# 31-FT4232_UART_TO_USB_BRIDG.net
KiCad netlist of a schematic drawn in Altium Designer
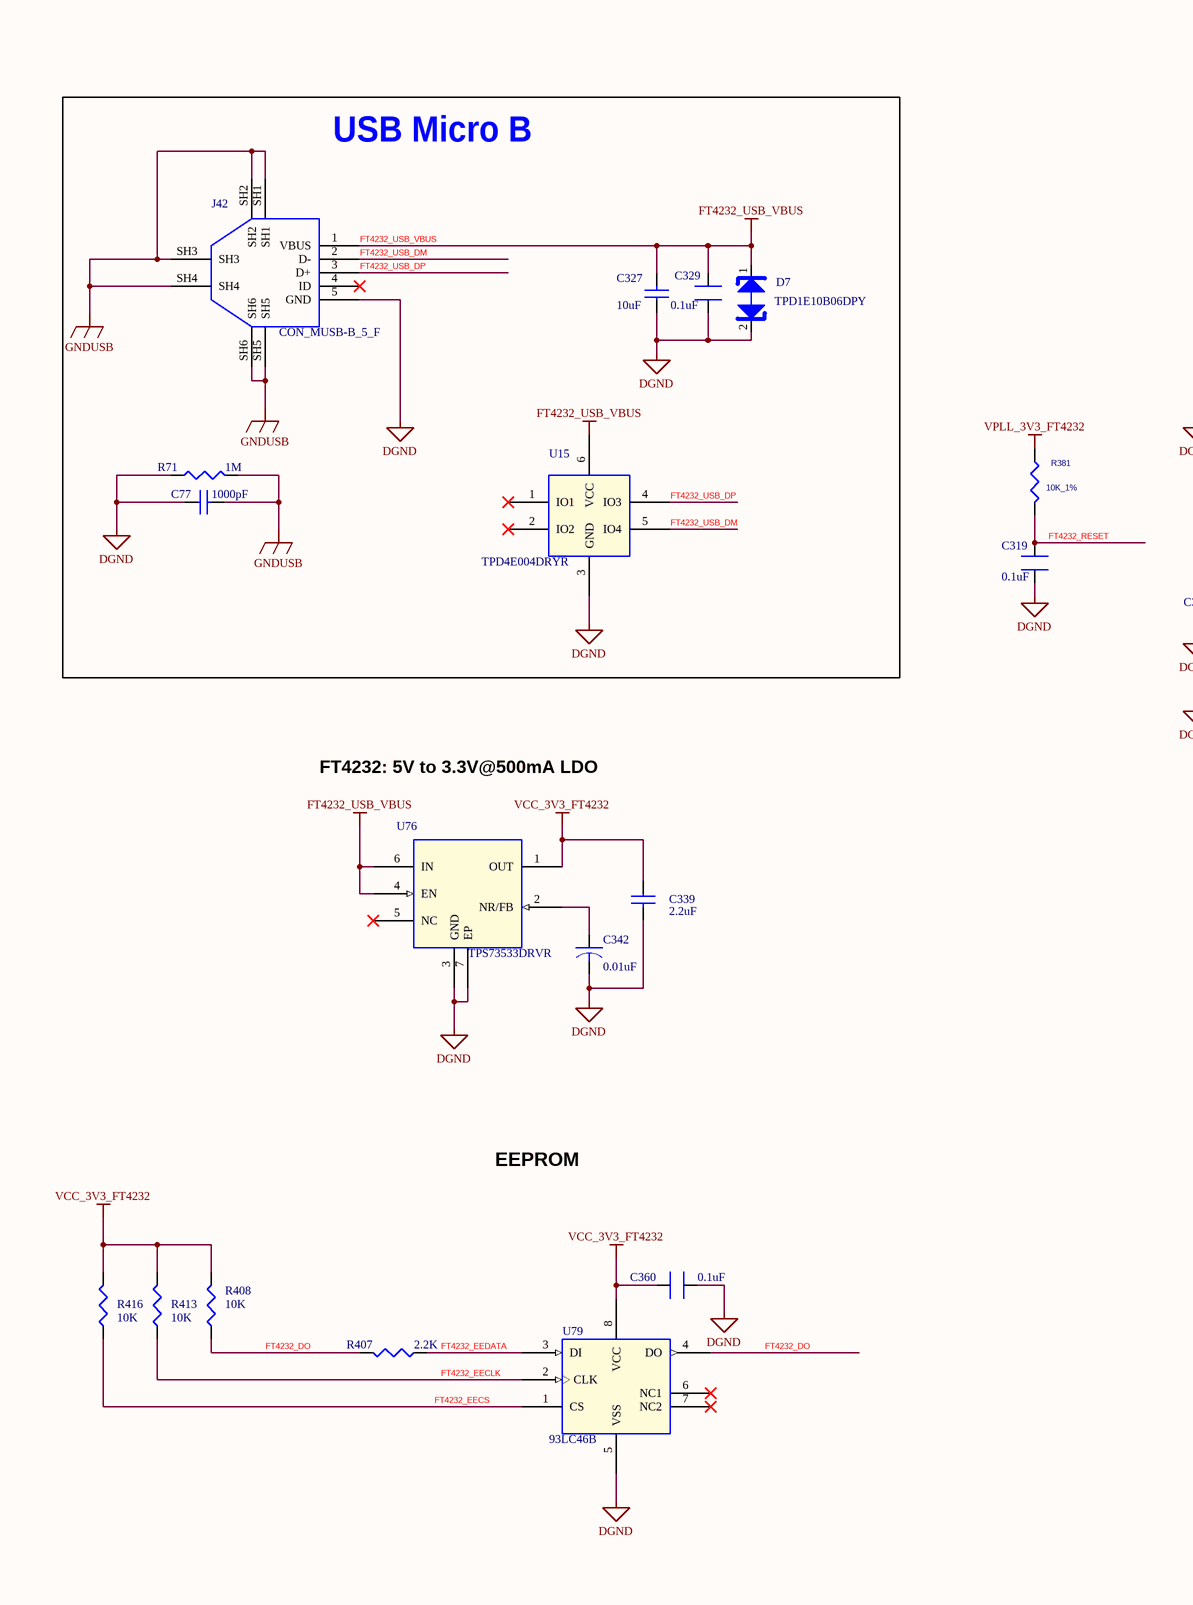
[diagram p0: 31-FT4232 UART TO USB BRIDG.SchDoc, left]
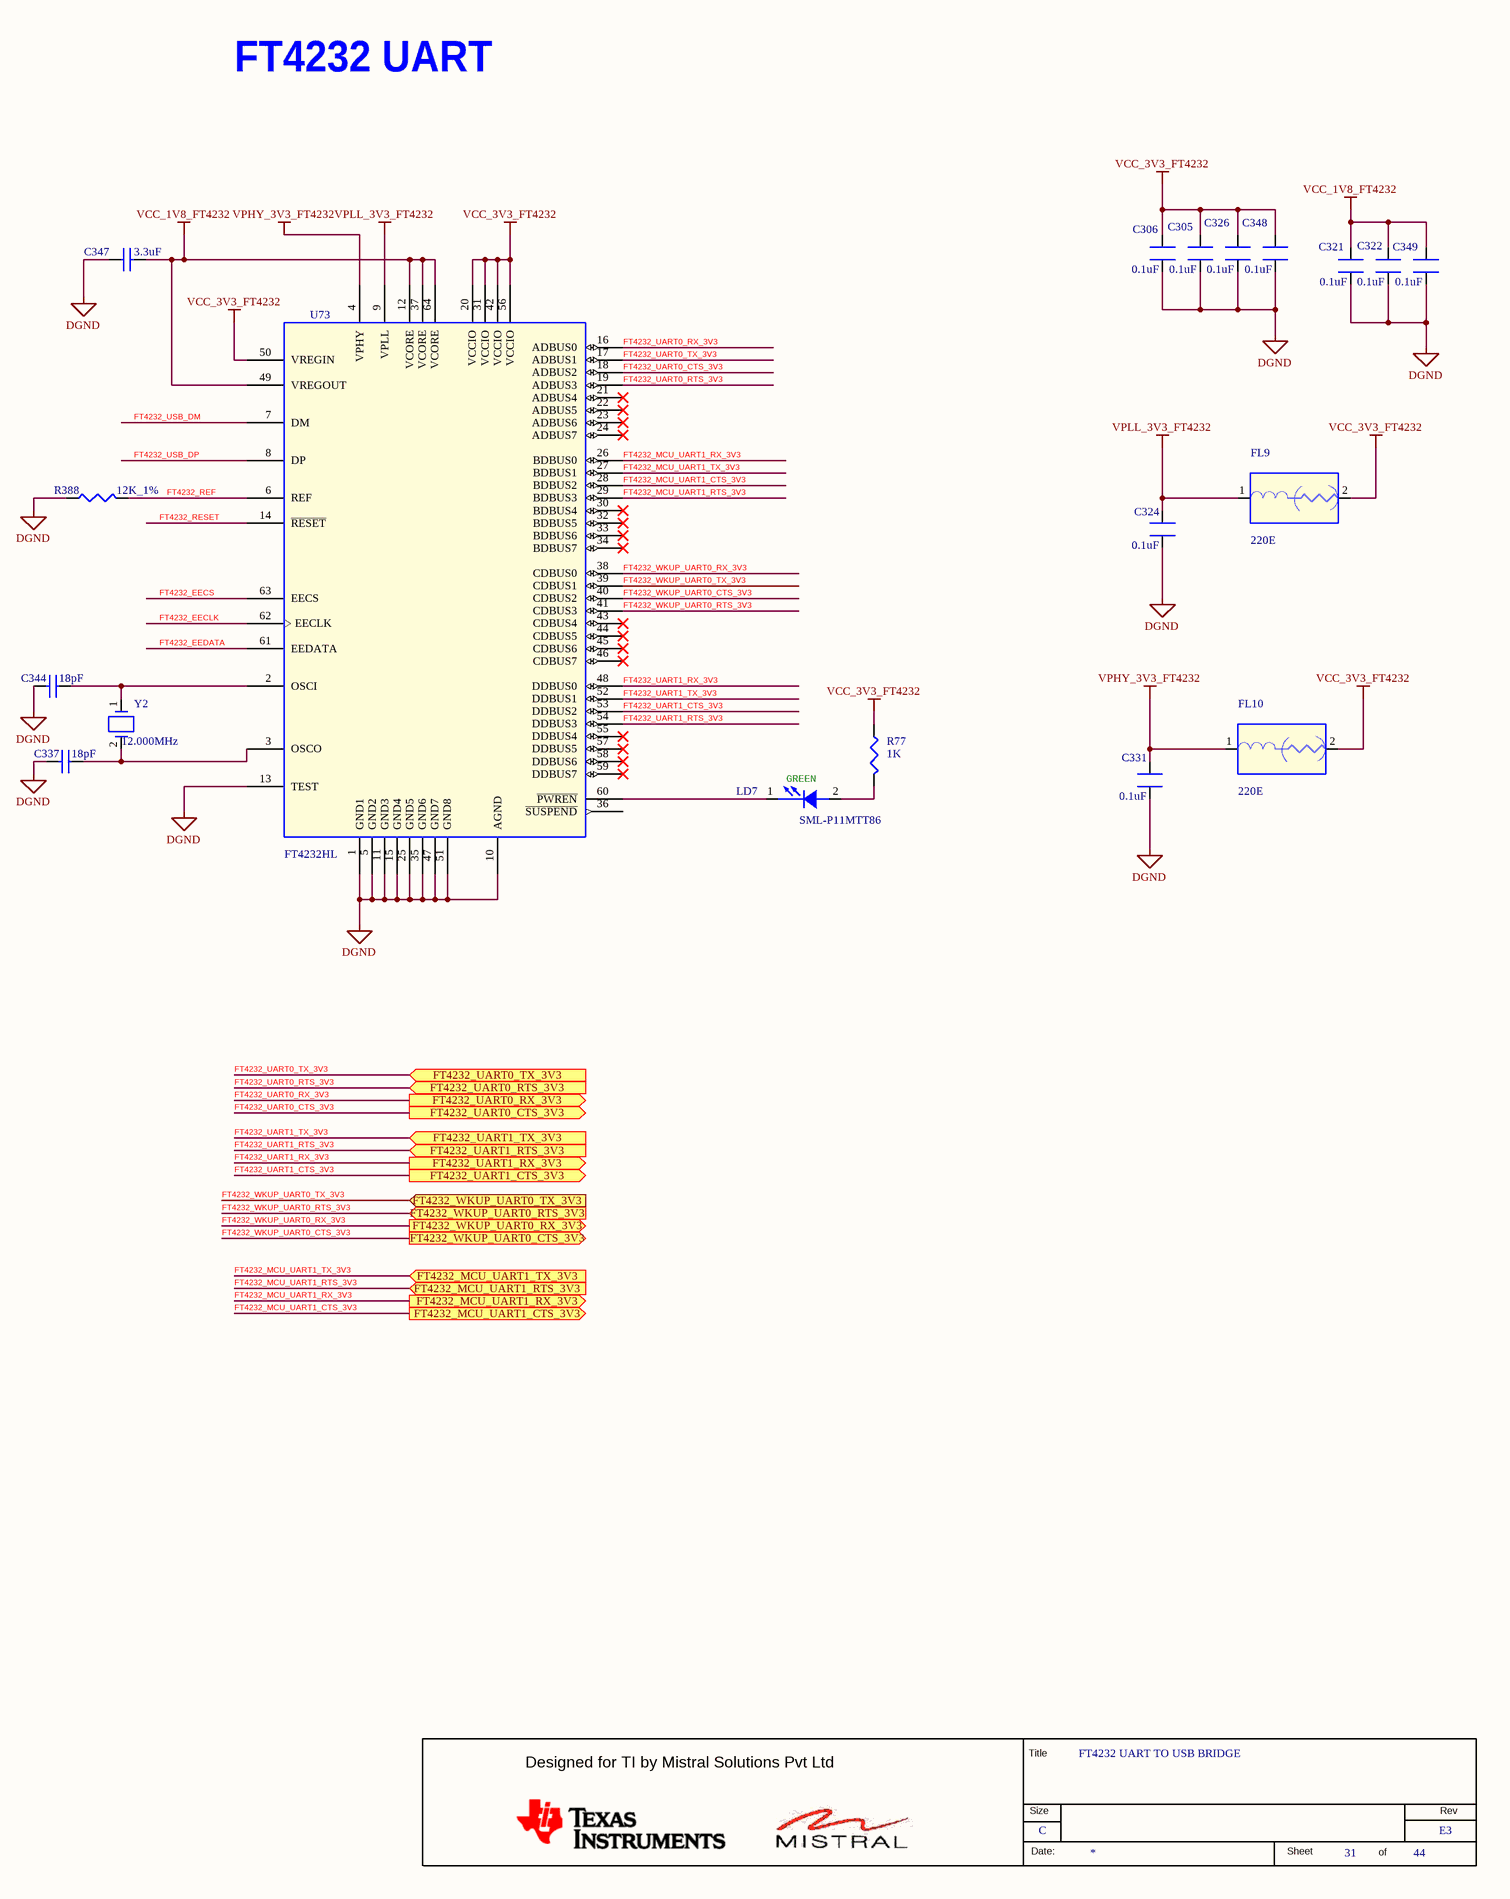
[diagram p1: 31-FT4232 UART TO USB BRIDG.SchDoc, right]

(export (version "E")
  (design (tool "Eeschema 10.0.6"))
  (components
    (comp (ref "C77")
      (value "1000pF")
      (footprint "CAP1206")
      (description "CAP CERAMIC 1000pF 2KV 10% X7R 1206")
      (fields (field (name "DISTRIBUTOR_PART_NUMBER") "478-2956-1-ND") (field (name "VOLTAGE") "2KV"))
      (libsource (lib "*") (part "CAP_Dup5"))
    )
    (comp (ref "C305")
      (value "0.1uF")
      (footprint "TMDX654GPEVM_BRD:CAP0201_0-5")
      (description "CAP CERAMIC 0.1uF 16V 10% X5R 0201")
      (fields
        (field (name "MISTRAL PART NO") "120009030072-R")
        (field (name "MFR_PART_NUMBER") "GRM033R61C104KE84J")
      )
      (libsource (lib "*") (part "CAP_Dup3"))
    )
    (comp (ref "C306")
      (value "0.1uF")
      (footprint "TMDX654GPEVM_BRD:CAP0201_0-5")
      (description "CAP CERAMIC 0.1uF 16V 10% X5R 0201")
      (fields (field (name "DISTRIBUTOR_PART_NUMBER") "490-16742-1-ND") (field (name "VOLTAGE") "16V"))
      (libsource (lib "*") (part "CAP_Dup3"))
    )
    (comp (ref "C319")
      (value "0.1uF")
      (footprint "TMDX654GPEVM_BRD:CAP0201_0-5")
      (description "CAP CERAMIC 0.1uF 16V 10% X5R 0201")
      (fields (field (name "DISTRIBUTOR_PART_NUMBER") "490-16742-1-ND") (field (name "VOLTAGE") "16V"))
      (libsource (lib "*") (part "CAP_Dup3"))
    )
    (comp (ref "C321")
      (value "0.1uF")
      (footprint "TMDX654GPEVM_BRD:CAP0201_0-5")
      (description "CAP CERAMIC 0.1uF 16V 10% X5R 0201")
      (fields
        (field (name "MISTRAL PART NO") "120009030072-R")
        (field (name "MFR_PART_NUMBER") "GRM033R61C104KE84J")
      )
      (libsource (lib "*") (part "CAP_Dup3"))
    )
    (comp (ref "C322")
      (value "0.1uF")
      (footprint "TMDX654GPEVM_BRD:CAP0201_0-5")
      (description "CAP CERAMIC 0.1uF 16V 10% X5R 0201")
      (fields (field (name "DISTRIBUTOR_PART_NUMBER") "490-16742-1-ND") (field (name "VOLTAGE") "16V"))
      (libsource (lib "*") (part "CAP_Dup3"))
    )
    (comp (ref "C324")
      (value "0.1uF")
      (footprint "TMDX654GPEVM_BRD:CAP0201_0-5")
      (description "CAP CERAMIC 0.1uF 16V 10% X5R 0201")
      (fields
        (field (name "MISTRAL PART NO") "120009030072-R")
        (field (name "MFR_PART_NUMBER") "GRM033R61C104KE84J")
      )
      (libsource (lib "*") (part "CAP_Dup3"))
    )
    (comp (ref "C326")
      (value "0.1uF")
      (footprint "TMDX654GPEVM_BRD:CAP0201_0-5")
      (description "CAP CERAMIC 0.1uF 16V 10% X5R 0201")
      (fields
        (field (name "MISTRAL PART NO") "120009030072-R")
        (field (name "MFR_PART_NUMBER") "GRM033R61C104KE84J")
      )
      (libsource (lib "*") (part "CAP_Dup3"))
    )
    (comp (ref "C327")
      (value "10uF")
      (footprint "CAP0603_1")
      (description "CAP CERAMIC 10uF 10V 10% X5R 0603")
      (fields (field (name "DISTRIBUTOR_PART_NUMBER") "478-10766-1-ND") (field (name "VOLTAGE") "10V"))
      (libsource (lib "*") (part "CAP_Dup5"))
    )
    (comp (ref "C329")
      (value "0.1uF")
      (footprint "TMDX654GPEVM_BRD:CAP0201_0-5")
      (description "CAP CERAMIC 0.1uF 16V 10% X5R 0201")
      (fields
        (field (name "MISTRAL PART NO") "120009030072-R")
        (field (name "MFR_PART_NUMBER") "GRM033R61C104KE84J")
      )
      (libsource (lib "*") (part "CAP_Dup3"))
    )
    (comp (ref "C331")
      (value "0.1uF")
      (footprint "TMDX654GPEVM_BRD:CAP0201_0-5")
      (description "CAP CERAMIC 0.1uF 16V 10% X5R 0201")
      (fields (field (name "DISTRIBUTOR_PART_NUMBER") "490-16742-1-ND") (field (name "VOLTAGE") "16V"))
      (libsource (lib "*") (part "CAP_Dup3"))
    )
    (comp (ref "C337")
      (value "18pF")
      (footprint "CAP0402_0-75")
      (description "CAP CERAMIC 18pF 50V 5% C0G(NP0) 0402")
      (fields (field (name "DISTRIBUTOR_PART_NUMBER") "490-5858-1-ND") (field (name "VOLTAGE") "50V"))
      (libsource (lib "*") (part "CAP_Dup5"))
    )
    (comp (ref "C339")
      (value "2.2uF")
      (footprint "CAP0402_0-75")
      (description "CAP CERAMIC 2.2uF 10V 20% X5R 0402")
      (fields (field (name "DISTRIBUTOR_PART_NUMBER") "490-12254-1-ND") (field (name "VOLTAGE") "10V"))
      (libsource (lib "*") (part "CAP_Dup5"))
    )
    (comp (ref "C342")
      (value "0.01uF")
      (footprint "CAP0201_0-5")
      (description "CAP CERAMIC 0.01uF 25V 10% X5R 0201")
      (fields (field (name "DISTRIBUTOR_PART_NUMBER") "GRM033R61E103KA12J-ND") (field (name "VOLTAGE") "25V"))
      (libsource (lib "*") (part "CAP"))
    )
    (comp (ref "C344")
      (value "18pF")
      (footprint "CAP0402_0-75")
      (description "CAP CERAMIC 18pF 50V 5% C0G(NP0) 0402")
      (fields
        (field (name "MISTRAL PART NO") "120014050002-R")
        (field (name "MFR_PART_NUMBER") "GRM1555C1H180JA01D")
      )
      (libsource (lib "*") (part "CAP_Dup5"))
    )
    (comp (ref "C347")
      (value "3.3uF")
      (footprint "CAP0402")
      (description "CAP CERAMIC 3.3uF 6.3V 20% X5R 0402")
      (fields (field (name "DISTRIBUTOR_PART_NUMBER") "445-7394-1-ND") (field (name "VOLTAGE") "6.3V"))
      (libsource (lib "*") (part "CAP_Dup5"))
    )
    (comp (ref "C348")
      (value "0.1uF")
      (footprint "TMDX654GPEVM_BRD:CAP0201_0-5")
      (description "CAP CERAMIC 0.1uF 16V 10% X5R 0201")
      (fields (field (name "DISTRIBUTOR_PART_NUMBER") "490-16742-1-ND") (field (name "VOLTAGE") "16V"))
      (libsource (lib "*") (part "CAP_Dup3"))
    )
    (comp (ref "C349")
      (value "0.1uF")
      (footprint "TMDX654GPEVM_BRD:CAP0201_0-5")
      (description "CAP CERAMIC 0.1uF 16V 10% X5R 0201")
      (fields (field (name "DISTRIBUTOR_PART_NUMBER") "490-16742-1-ND") (field (name "VOLTAGE") "16V"))
      (libsource (lib "*") (part "CAP_Dup3"))
    )
    (comp (ref "C360")
      (value "0.1uF")
      (footprint "TMDX654GPEVM_BRD:CAP0201_0-5")
      (description "CAP CERAMIC 0.1uF 16V 10% X5R 0201")
      (fields (field (name "DISTRIBUTOR_PART_NUMBER") "490-16742-1-ND") (field (name "VOLTAGE") "16V"))
      (libsource (lib "*") (part "CAP_Dup3"))
    )
    (comp (ref "D7")
      (value "TPD1E10B06DPY")
      (footprint "DIO_DFN0402")
      (description "DIODE 1CH ESD PROTECTION SMD(0402)")
      (fields (field (name "DISTRIBUTOR_PART_NUMBER") "296-30406-1-ND") (field (name "VOLTAGE") "NA"))
      (libsource (lib "*") (part "DIODE_PESD"))
    )
    (comp (ref "FL9")
      (value "220E")
      (footprint "EMIFIL_BLM15A_0402")
      (description "FERRITE CHIP 220E 0.3A 0402")
      (fields (field (name "DISTRIBUTOR_PART_NUMBER") "490-5197-1-ND") (field (name "VOLTAGE") "NA"))
      (libsource (lib "*") (part "EMIFILTER_IND"))
    )
    (comp (ref "FL10")
      (value "220E")
      (footprint "EMIFIL_BLM15A_0402")
      (description "FERRITE CHIP 220E 0.3A 0402")
      (fields
        (field (name "MISTRAL PART NO") "130013100020-R")
        (field (name "MFR_PART_NUMBER") "BLM15GG221SN1D")
      )
      (libsource (lib "*") (part "EMIFILTER_IND"))
    )
    (comp (ref "J42")
      (value "CON_MUSB-B_5_F")
      (footprint "CON_MUSBB5_1051640001_S_R_S_2-5")
      (description "CON MICRO USB-B TYPE 5POS FEMALE RT SMD")
      (fields (field (name "DISTRIBUTOR_PART_NUMBER") "WM11263CT-ND") (field (name "VOLTAGE") "NA"))
      (libsource (lib "*") (part "CON_MUSB-B_5_1051640001"))
    )
    (comp (ref "LD7")
      (value "SML-P11MTT86")
      (footprint "LED_0402_0-3")
      (description "DIODE LED GREEN 0402")
      (fields (field (name "VOLTAGE") "NA") (field (name "MISTRAL PART NO") "130010060029-R"))
      (libsource (lib "*") (part "DIODE_LED"))
    )
    (comp (ref "R71")
      (value "1M")
      (footprint "RES0603_0-75")
      (description "RES 1M 1/10W 5% 0603")
      (fields
        (field (name "MISTRAL PART NO") "110009030413-R")
        (field (name "MFR_PART_NUMBER") "ERJ-3GEYJ105V")
      )
      (libsource (lib "*") (part "RESISTOR_Dup5"))
    )
    (comp (ref "R77")
      (value "1K")
      (footprint "RES0201")
      (description "RES 1K 1/20W 5% 0201")
      (fields
        (field (name "MISTRAL PART NO") "110015080014-R")
        (field (name "MFR_PART_NUMBER") "CRCW02011K00FKED")
      )
      (libsource (lib "*") (part "RESISTOR_Dup5"))
    )
    (comp (ref "R381")
      (value "10K_1%")
      (footprint "RES0402_0-5")
      (description "RES 10K 1/16W 1% 0402")
      (fields (field (name "VOLTAGE") "NA") (field (name "MISTRAL PART NO") "110009030220-P"))
      (libsource (lib "*") (part "RESISTOR_Dup2"))
    )
    (comp (ref "R388")
      (value "12K_1%")
      (footprint "RES0402")
      (description "RES 12K 1/16W 1% 0402")
      (fields (field (name "DISTRIBUTOR_PART_NUMBER") "P12.0KLCT-ND") (field (name "VOLTAGE") "NA"))
      (libsource (lib "*") (part "RESISTOR_Dup5"))
    )
    (comp (ref "R407")
      (value "2.2K")
      (footprint "RES0402_0-5")
      (description "RES 2.2K 1/16W 5% 0402")
      (fields (field (name "DISTRIBUTOR_PART_NUMBER") "311-2.2KJRCT-ND") (field (name "VOLTAGE") "NA"))
      (libsource (lib "*") (part "RESISTOR_Dup5"))
    )
    (comp (ref "R408")
      (value "10K")
      (footprint "RES0402_0-5")
      (description "RES 10K 1/16W 5% 0402")
      (fields
        (field (name "MISTRAL PART NO") "110009030208-R")
        (field (name "MFR_PART_NUMBER") "RC0402JR-0710KL")
      )
      (libsource (lib "*") (part "RESISTOR_Dup5"))
    )
    (comp (ref "R413")
      (value "10K")
      (footprint "RES0402_0-5")
      (description "RES 10K 1/16W 5% 0402")
      (fields
        (field (name "MISTRAL PART NO") "110009030208-R")
        (field (name "MFR_PART_NUMBER") "RC0402JR-0710KL")
      )
      (libsource (lib "*") (part "RESISTOR_Dup5"))
    )
    (comp (ref "R416")
      (value "10K")
      (footprint "RES0402_0-5")
      (description "RES 10K 1/16W 5% 0402")
      (fields (field (name "DISTRIBUTOR_PART_NUMBER") "311-10KJRCT-ND") (field (name "VOLTAGE") "NA"))
      (libsource (lib "*") (part "RESISTOR_Dup5"))
    )
    (comp (ref "U15")
      (value "TPD4E004DRYR")
      (footprint "SON6_19-68_60X45")
      (description "IC 4CH ESD-PROT ARRAY SON6")
      (fields
        (field (name "DISTRIBUTOR_PART_NUMBER") "296-23618-1-ND")
        (field (name "MISTRAL PART NO") "141010020012-P")
      )
      (libsource (lib "*") (part "TPD4E004_SON6"))
    )
    (comp (ref "U73")
      (value "FT4232HL")
      (footprint "TMDX654GPEVM_BRD:LQFP64_19-68_390X390_1-6")
      (description "IC HIGH SPEED QUAD USB UART LQFP64")
      (fields
        (field (name "MISTRAL PART NO") "141013080006-R")
        (field (name "MFR_PART_NUMBER") "FT4232HL-REEL")
      )
      (libsource (lib "*") (part "FT4232H _LQFP64"))
    )
    (comp (ref "U76")
      (value "TPS73533DRVR")
      (footprint "SON6_25-59_85X85")
      (description "IC 500mA LOW DROPOUT REGULATOR SON6")
      (fields (field (name "MISTRAL PART NO") "142014100001-R") (field (name "TOLERANCE") "NA"))
      (libsource (lib "*") (part "TPS73501DRVR_SON6"))
    )
    (comp (ref "U79")
      (value "93LC46B")
      (footprint "MSOP8_25-59_125X125_1-1")
      (description "IC 1K MICROWIRE COMPATIBLE SERIAL EEPROM MSOP8")
      (fields
        (field (name "DISTRIBUTOR_PART_NUMBER") "93LC46B-I/MS-ND")
        (field (name "VOLTAGE") "NA")
        (field (name "LIBRARY PATH") "Y~{:}MIS_DATABAS~{E}Librar~{y}ALTIUM_TOO~{L}SCHEMATICS_PART~{S}MS_MISCMEMORY_Library.schlib")
      )
      (libsource (lib "*") (part "93LC46B_MSOP8"))
    )
    (comp (ref "Y2")
      (value "12.000MHz")
      (footprint "XTAL_ABM3_205X130_SMD")
      (description "CRY 12MHz SMD")
      (fields (field (name "DISTRIBUTOR_PART_NUMBER") "535-10634-1-ND") (field (name "VOLTAGE") "NA"))
      (libsource (lib "*") (part "CRY"))
    )
  )
  (nets
    (net (code "1") (name "/FT4232_DO") (class "Default")
      (node (ref "R407") (pin "2") (pinfunction "2_2") (pintype "passive"))
      (node (ref "R408") (pin "1") (pinfunction "1_1") (pintype "passive"))
      (node (ref "U79") (pin "4") (pinfunction "DO_4") (pintype "output"))
    )
    (net (code "2") (name "/FT4232_EECLK") (class "Default")
      (node (ref "R413") (pin "1") (pinfunction "1_1") (pintype "passive"))
      (node (ref "U73") (pin "62") (pinfunction "EECLK_62") (pintype "passive"))
      (node (ref "U79") (pin "2") (pinfunction "CLK_2") (pintype "input"))
    )
    (net (code "3") (name "/FT4232_EECS") (class "Default")
      (node (ref "R416") (pin "1") (pinfunction "1_1") (pintype "passive"))
      (node (ref "U73") (pin "63") (pinfunction "EECS_63") (pintype "passive"))
      (node (ref "U79") (pin "1") (pinfunction "CS_1") (pintype "passive"))
    )
    (net (code "4") (name "/FT4232_EEDATA") (class "Default")
      (node (ref "R407") (pin "1") (pinfunction "1_1") (pintype "passive"))
      (node (ref "U73") (pin "61") (pinfunction "EEDATA_61") (pintype "passive"))
      (node (ref "U79") (pin "3") (pinfunction "DI_3") (pintype "input"))
    )
    (net (code "5") (name "/FT4232_MCU_UART1_CTS_3V3") (class "Default")
      (node (ref "U73") (pin "28") (pinfunction "BDBUS2_28") (pintype "bidirectional"))
    )
    (net (code "6") (name "/FT4232_MCU_UART1_RTS_3V3") (class "Default")
      (node (ref "U73") (pin "29") (pinfunction "BDBUS3_29") (pintype "bidirectional"))
    )
    (net (code "7") (name "/FT4232_MCU_UART1_RX_3V3") (class "Default")
      (node (ref "U73") (pin "26") (pinfunction "BDBUS0_26") (pintype "bidirectional"))
    )
    (net (code "8") (name "/FT4232_MCU_UART1_TX_3V3") (class "Default")
      (node (ref "U73") (pin "27") (pinfunction "BDBUS1_27") (pintype "bidirectional"))
    )
    (net (code "9") (name "/FT4232_REF") (class "Default")
      (node (ref "R388") (pin "2") (pinfunction "2_2") (pintype "passive"))
      (node (ref "U73") (pin "6") (pinfunction "REF_6") (pintype "passive"))
    )
    (net (code "10") (name "/FT4232_RESET") (class "Default")
      (node (ref "C319") (pin "2") (pinfunction "2_2") (pintype "passive"))
      (node (ref "R381") (pin "1") (pinfunction "1_1") (pintype "passive"))
      (node (ref "U73") (pin "14") (pinfunction "~{RESET}_14") (pintype "passive"))
    )
    (net (code "11") (name "/FT4232_UART0_CTS_3V3") (class "Default")
      (node (ref "U73") (pin "18") (pinfunction "ADBUS2_18") (pintype "bidirectional"))
    )
    (net (code "12") (name "/FT4232_UART0_RTS_3V3") (class "Default")
      (node (ref "U73") (pin "19") (pinfunction "ADBUS3_19") (pintype "bidirectional"))
    )
    (net (code "13") (name "/FT4232_UART0_RX_3V3") (class "Default")
      (node (ref "U73") (pin "16") (pinfunction "ADBUS0_16") (pintype "bidirectional"))
    )
    (net (code "14") (name "/FT4232_UART0_TX_3V3") (class "Default")
      (node (ref "U73") (pin "17") (pinfunction "ADBUS1_17") (pintype "bidirectional"))
    )
    (net (code "15") (name "/FT4232_UART1_CTS_3V3") (class "Default")
      (node (ref "U73") (pin "53") (pinfunction "DDBUS2_53") (pintype "bidirectional"))
    )
    (net (code "16") (name "/FT4232_UART1_RTS_3V3") (class "Default")
      (node (ref "U73") (pin "54") (pinfunction "DDBUS3_54") (pintype "bidirectional"))
    )
    (net (code "17") (name "/FT4232_UART1_RX_3V3") (class "Default")
      (node (ref "U73") (pin "48") (pinfunction "DDBUS0_48") (pintype "bidirectional"))
    )
    (net (code "18") (name "/FT4232_UART1_TX_3V3") (class "Default")
      (node (ref "U73") (pin "52") (pinfunction "DDBUS1_52") (pintype "bidirectional"))
    )
    (net (code "19") (name "/FT4232_USB_DM") (class "Default")
      (node (ref "J42") (pin "2") (pinfunction "D-_2") (pintype "passive"))
      (node (ref "U15") (pin "5") (pinfunction "IO4_5") (pintype "passive"))
      (node (ref "U73") (pin "7") (pinfunction "DM_7") (pintype "passive"))
    )
    (net (code "20") (name "/FT4232_USB_DP") (class "Default")
      (node (ref "J42") (pin "3") (pinfunction "D+_3") (pintype "passive"))
      (node (ref "U15") (pin "4") (pinfunction "IO3_4") (pintype "passive"))
      (node (ref "U73") (pin "8") (pinfunction "DP_8") (pintype "passive"))
    )
    (net (code "21") (name "/FT4232_WKUP_UART0_CTS_3V3") (class "Default")
      (node (ref "U73") (pin "40") (pinfunction "CDBUS2_40") (pintype "bidirectional"))
    )
    (net (code "22") (name "/FT4232_WKUP_UART0_RTS_3V3") (class "Default")
      (node (ref "U73") (pin "41") (pinfunction "CDBUS3_41") (pintype "bidirectional"))
    )
    (net (code "23") (name "/FT4232_WKUP_UART0_RX_3V3") (class "Default")
      (node (ref "U73") (pin "38") (pinfunction "CDBUS0_38") (pintype "bidirectional"))
    )
    (net (code "24") (name "/FT4232_WKUP_UART0_TX_3V3") (class "Default")
      (node (ref "U73") (pin "39") (pinfunction "CDBUS1_39") (pintype "bidirectional"))
    )
    (net (code "25") (name "DGND") (class "Default")
      (node (ref "C305") (pin "1") (pinfunction "1_1") (pintype "passive"))
      (node (ref "C306") (pin "1") (pinfunction "1_1") (pintype "passive"))
      (node (ref "C319") (pin "1") (pinfunction "1_1") (pintype "passive"))
      (node (ref "C321") (pin "1") (pinfunction "1_1") (pintype "passive"))
      (node (ref "C322") (pin "1") (pinfunction "1_1") (pintype "passive"))
      (node (ref "C324") (pin "1") (pinfunction "1_1") (pintype "passive"))
      (node (ref "C326") (pin "1") (pinfunction "1_1") (pintype "passive"))
      (node (ref "C327") (pin "1") (pinfunction "1_1") (pintype "passive"))
      (node (ref "C329") (pin "1") (pinfunction "1_1") (pintype "passive"))
      (node (ref "C331") (pin "1") (pinfunction "1_1") (pintype "passive"))
      (node (ref "C337") (pin "2") (pinfunction "2_2") (pintype "passive"))
      (node (ref "C339") (pin "2") (pinfunction "2_2") (pintype "passive"))
      (node (ref "C342") (pin "2") (pinfunction "2_2") (pintype "passive"))
      (node (ref "C344") (pin "2") (pinfunction "2_2") (pintype "passive"))
      (node (ref "C347") (pin "1") (pinfunction "1_1") (pintype "passive"))
      (node (ref "C348") (pin "1") (pinfunction "1_1") (pintype "passive"))
      (node (ref "C349") (pin "1") (pinfunction "1_1") (pintype "passive"))
      (node (ref "C360") (pin "1") (pinfunction "1_1") (pintype "passive"))
      (node (ref "C77") (pin "1") (pinfunction "1_1") (pintype "passive"))
      (node (ref "D7") (pin "2") (pinfunction "A_2") (pintype "passive"))
      (node (ref "J42") (pin "5") (pinfunction "GND_5") (pintype "power_in"))
      (node (ref "R388") (pin "1") (pinfunction "1_1") (pintype "passive"))
      (node (ref "R71") (pin "1") (pinfunction "1_1") (pintype "passive"))
      (node (ref "U15") (pin "3") (pinfunction "GND_3") (pintype "power_in"))
      (node (ref "U73") (pin "1") (pinfunction "GND1_1") (pintype "power_in"))
      (node (ref "U73") (pin "10") (pinfunction "AGND_10") (pintype "power_in"))
      (node (ref "U73") (pin "11") (pinfunction "GND3_11") (pintype "power_in"))
      (node (ref "U73") (pin "13") (pinfunction "TEST_13") (pintype "passive"))
      (node (ref "U73") (pin "15") (pinfunction "GND4_15") (pintype "power_in"))
      (node (ref "U73") (pin "25") (pinfunction "GND5_25") (pintype "power_in"))
      (node (ref "U73") (pin "35") (pinfunction "GND6_35") (pintype "power_in"))
      (node (ref "U73") (pin "47") (pinfunction "GND7_47") (pintype "power_in"))
      (node (ref "U73") (pin "5") (pinfunction "GND2_5") (pintype "power_in"))
      (node (ref "U73") (pin "51") (pinfunction "GND8_51") (pintype "power_in"))
      (node (ref "U76") (pin "3") (pinfunction "GND_3") (pintype "power_in"))
      (node (ref "U76") (pin "7") (pinfunction "EP_7") (pintype "power_in"))
      (node (ref "U79") (pin "5") (pinfunction "VSS_5") (pintype "power_in"))
    )
    (net (code "26") (name "FT4232_USB_VBUS") (class "Default")
      (node (ref "C327") (pin "2") (pinfunction "2_2") (pintype "passive"))
      (node (ref "C329") (pin "2") (pinfunction "2_2") (pintype "passive"))
      (node (ref "D7") (pin "1") (pinfunction "K_1") (pintype "passive"))
      (node (ref "J42") (pin "1") (pinfunction "VBUS_1") (pintype "passive"))
      (node (ref "U15") (pin "6") (pinfunction "VCC_6") (pintype "power_in"))
      (node (ref "U76") (pin "4") (pinfunction "EN_4") (pintype "input"))
      (node (ref "U76") (pin "6") (pinfunction "IN_6") (pintype "power_in"))
    )
    (net (code "27") (name "GNDUSB") (class "Default")
      (node (ref "C77") (pin "2") (pinfunction "2_2") (pintype "passive"))
      (node (ref "J42") (pin "SH1") (pinfunction "SH1_SH1") (pintype "passive"))
      (node (ref "J42") (pin "SH2") (pinfunction "SH2_SH2") (pintype "passive"))
      (node (ref "J42") (pin "SH3") (pinfunction "SH3_SH3") (pintype "passive"))
      (node (ref "J42") (pin "SH4") (pinfunction "SH4_SH4") (pintype "passive"))
      (node (ref "J42") (pin "SH5") (pinfunction "SH5_SH5") (pintype "passive"))
      (node (ref "J42") (pin "SH6") (pinfunction "SH6_SH6") (pintype "passive"))
      (node (ref "R71") (pin "2") (pinfunction "2_2") (pintype "passive"))
    )
    (net (code "28") (name "Net-(LD7-ANODE)") (class "Default")
      (node (ref "LD7") (pin "2") (pinfunction "ANODE_2") (pintype "passive"))
      (node (ref "R77") (pin "2") (pinfunction "2_2") (pintype "passive"))
    )
    (net (code "29") (name "Net-(LD7-CATHODE)") (class "Default")
      (node (ref "LD7") (pin "1") (pinfunction "CATHODE_1") (pintype "passive"))
      (node (ref "U73") (pin "60") (pinfunction "~{PWREN}_60") (pintype "passive"))
    )
    (net (code "30") (name "Net-(U73-OSCI)") (class "Default")
      (node (ref "C344") (pin "1") (pinfunction "1_1") (pintype "passive"))
      (node (ref "U73") (pin "2") (pinfunction "OSCI_2") (pintype "passive"))
      (node (ref "Y2") (pin "1") (pinfunction "1_1") (pintype "passive"))
    )
    (net (code "31") (name "Net-(U73-OSCO)") (class "Default")
      (node (ref "C337") (pin "1") (pinfunction "1_1") (pintype "passive"))
      (node (ref "U73") (pin "3") (pinfunction "OSCO_3") (pintype "passive"))
      (node (ref "Y2") (pin "2") (pinfunction "2_2") (pintype "passive"))
    )
    (net (code "32") (name "Net-(U76-NR{slash}FB)") (class "Default")
      (node (ref "C342") (pin "1") (pinfunction "1_1") (pintype "passive"))
      (node (ref "U76") (pin "2") (pinfunction "NR/FB_2") (pintype "input"))
    )
    (net (code "33") (name "VCC_1V8_FT4232") (class "Default")
      (node (ref "C321") (pin "2") (pinfunction "2_2") (pintype "passive"))
      (node (ref "C322") (pin "2") (pinfunction "2_2") (pintype "passive"))
      (node (ref "C347") (pin "2") (pinfunction "2_2") (pintype "passive"))
      (node (ref "C349") (pin "2") (pinfunction "2_2") (pintype "passive"))
      (node (ref "U73") (pin "12") (pinfunction "VCORE_12") (pintype "power_in"))
      (node (ref "U73") (pin "37") (pinfunction "VCORE_37") (pintype "power_in"))
      (node (ref "U73") (pin "49") (pinfunction "VREGOUT_49") (pintype "power_in"))
      (node (ref "U73") (pin "64") (pinfunction "VCORE_64") (pintype "power_in"))
    )
    (net (code "34") (name "VCC_3V3_FT4232") (class "Default")
      (node (ref "C305") (pin "2") (pinfunction "2_2") (pintype "passive"))
      (node (ref "C306") (pin "2") (pinfunction "2_2") (pintype "passive"))
      (node (ref "C326") (pin "2") (pinfunction "2_2") (pintype "passive"))
      (node (ref "C339") (pin "1") (pinfunction "1_1") (pintype "passive"))
      (node (ref "C348") (pin "2") (pinfunction "2_2") (pintype "passive"))
      (node (ref "C360") (pin "2") (pinfunction "2_2") (pintype "passive"))
      (node (ref "FL10") (pin "2") (pinfunction "2_2") (pintype "passive"))
      (node (ref "FL9") (pin "2") (pinfunction "2_2") (pintype "passive"))
      (node (ref "R408") (pin "2") (pinfunction "2_2") (pintype "passive"))
      (node (ref "R413") (pin "2") (pinfunction "2_2") (pintype "passive"))
      (node (ref "R416") (pin "2") (pinfunction "2_2") (pintype "passive"))
      (node (ref "R77") (pin "1") (pinfunction "1_1") (pintype "passive"))
      (node (ref "U73") (pin "20") (pinfunction "VCCIO_20") (pintype "power_in"))
      (node (ref "U73") (pin "31") (pinfunction "VCCIO_31") (pintype "power_in"))
      (node (ref "U73") (pin "42") (pinfunction "VCCIO_42") (pintype "power_in"))
      (node (ref "U73") (pin "50") (pinfunction "VREGIN_50") (pintype "power_in"))
      (node (ref "U73") (pin "56") (pinfunction "VCCIO_56") (pintype "power_in"))
      (node (ref "U76") (pin "1") (pinfunction "OUT_1") (pintype "power_in"))
      (node (ref "U79") (pin "8") (pinfunction "VCC_8") (pintype "power_in"))
    )
    (net (code "35") (name "VPHY_3V3_FT4232") (class "Default")
      (node (ref "C331") (pin "2") (pinfunction "2_2") (pintype "passive"))
      (node (ref "FL10") (pin "1") (pinfunction "1_1") (pintype "passive"))
      (node (ref "U73") (pin "4") (pinfunction "VPHY_4") (pintype "power_in"))
    )
    (net (code "36") (name "VPLL_3V3_FT4232") (class "Default")
      (node (ref "C324") (pin "2") (pinfunction "2_2") (pintype "passive"))
      (node (ref "FL9") (pin "1") (pinfunction "1_1") (pintype "passive"))
      (node (ref "R381") (pin "2") (pinfunction "2_2") (pintype "passive"))
      (node (ref "U73") (pin "9") (pinfunction "VPLL_9") (pintype "power_in"))
    )
    (net (code "37") (name "unconnected-(J42-ID-Pad4)") (class "Default")
      (node (ref "J42") (pin "4") (pinfunction "ID_4") (pintype "passive+no_connect"))
    )
    (net (code "38") (name "unconnected-(U15-IO1-Pad1)") (class "Default")
      (node (ref "U15") (pin "1") (pinfunction "IO1_1") (pintype "passive+no_connect"))
    )
    (net (code "39") (name "unconnected-(U15-IO2-Pad2)") (class "Default")
      (node (ref "U15") (pin "2") (pinfunction "IO2_2") (pintype "passive+no_connect"))
    )
    (net (code "40") (name "unconnected-(U73-ADBUS4-Pad21)") (class "Default")
      (node (ref "U73") (pin "21") (pinfunction "ADBUS4_21") (pintype "bidirectional+no_connect"))
    )
    (net (code "41") (name "unconnected-(U73-ADBUS5-Pad22)") (class "Default")
      (node (ref "U73") (pin "22") (pinfunction "ADBUS5_22") (pintype "bidirectional+no_connect"))
    )
    (net (code "42") (name "unconnected-(U73-ADBUS6-Pad23)") (class "Default")
      (node (ref "U73") (pin "23") (pinfunction "ADBUS6_23") (pintype "bidirectional+no_connect"))
    )
    (net (code "43") (name "unconnected-(U73-ADBUS7-Pad24)") (class "Default")
      (node (ref "U73") (pin "24") (pinfunction "ADBUS7_24") (pintype "bidirectional+no_connect"))
    )
    (net (code "44") (name "unconnected-(U73-BDBUS4-Pad30)") (class "Default")
      (node (ref "U73") (pin "30") (pinfunction "BDBUS4_30") (pintype "bidirectional+no_connect"))
    )
    (net (code "45") (name "unconnected-(U73-BDBUS5-Pad32)") (class "Default")
      (node (ref "U73") (pin "32") (pinfunction "BDBUS5_32") (pintype "bidirectional+no_connect"))
    )
    (net (code "46") (name "unconnected-(U73-BDBUS6-Pad33)") (class "Default")
      (node (ref "U73") (pin "33") (pinfunction "BDBUS6_33") (pintype "bidirectional+no_connect"))
    )
    (net (code "47") (name "unconnected-(U73-BDBUS7-Pad34)") (class "Default")
      (node (ref "U73") (pin "34") (pinfunction "BDBUS7_34") (pintype "bidirectional+no_connect"))
    )
    (net (code "48") (name "unconnected-(U73-CDBUS4-Pad43)") (class "Default")
      (node (ref "U73") (pin "43") (pinfunction "CDBUS4_43") (pintype "bidirectional+no_connect"))
    )
    (net (code "49") (name "unconnected-(U73-CDBUS5-Pad44)") (class "Default")
      (node (ref "U73") (pin "44") (pinfunction "CDBUS5_44") (pintype "bidirectional+no_connect"))
    )
    (net (code "50") (name "unconnected-(U73-CDBUS6-Pad45)") (class "Default")
      (node (ref "U73") (pin "45") (pinfunction "CDBUS6_45") (pintype "bidirectional+no_connect"))
    )
    (net (code "51") (name "unconnected-(U73-CDBUS7-Pad46)") (class "Default")
      (node (ref "U73") (pin "46") (pinfunction "CDBUS7_46") (pintype "bidirectional+no_connect"))
    )
    (net (code "52") (name "unconnected-(U73-DDBUS4-Pad55)") (class "Default")
      (node (ref "U73") (pin "55") (pinfunction "DDBUS4_55") (pintype "bidirectional+no_connect"))
    )
    (net (code "53") (name "unconnected-(U73-DDBUS5-Pad57)") (class "Default")
      (node (ref "U73") (pin "57") (pinfunction "DDBUS5_57") (pintype "bidirectional+no_connect"))
    )
    (net (code "54") (name "unconnected-(U73-DDBUS6-Pad58)") (class "Default")
      (node (ref "U73") (pin "58") (pinfunction "DDBUS6_58") (pintype "bidirectional+no_connect"))
    )
    (net (code "55") (name "unconnected-(U73-DDBUS7-Pad59)") (class "Default")
      (node (ref "U73") (pin "59") (pinfunction "DDBUS7_59") (pintype "bidirectional+no_connect"))
    )
    (net (code "56") (name "unconnected-(U73-~{SUSPEND}-Pad36)") (class "Default")
      (node (ref "U73") (pin "36") (pinfunction "~{SUSPEND}_36") (pintype "output"))
    )
    (net (code "57") (name "unconnected-(U76-NC-Pad5)") (class "Default")
      (node (ref "U76") (pin "5") (pinfunction "NC_5") (pintype "passive+no_connect"))
    )
    (net (code "58") (name "unconnected-(U79-NC1-Pad6)") (class "Default")
      (node (ref "U79") (pin "6") (pinfunction "NC1_6") (pintype "passive+no_connect"))
    )
    (net (code "59") (name "unconnected-(U79-NC2-Pad7)") (class "Default")
      (node (ref "U79") (pin "7") (pinfunction "NC2_7") (pintype "passive+no_connect"))
    )
  )
)
